# bloodhound_gprs_0_beta.net
KiCad netlist of a schematic drawn in Altium Designer
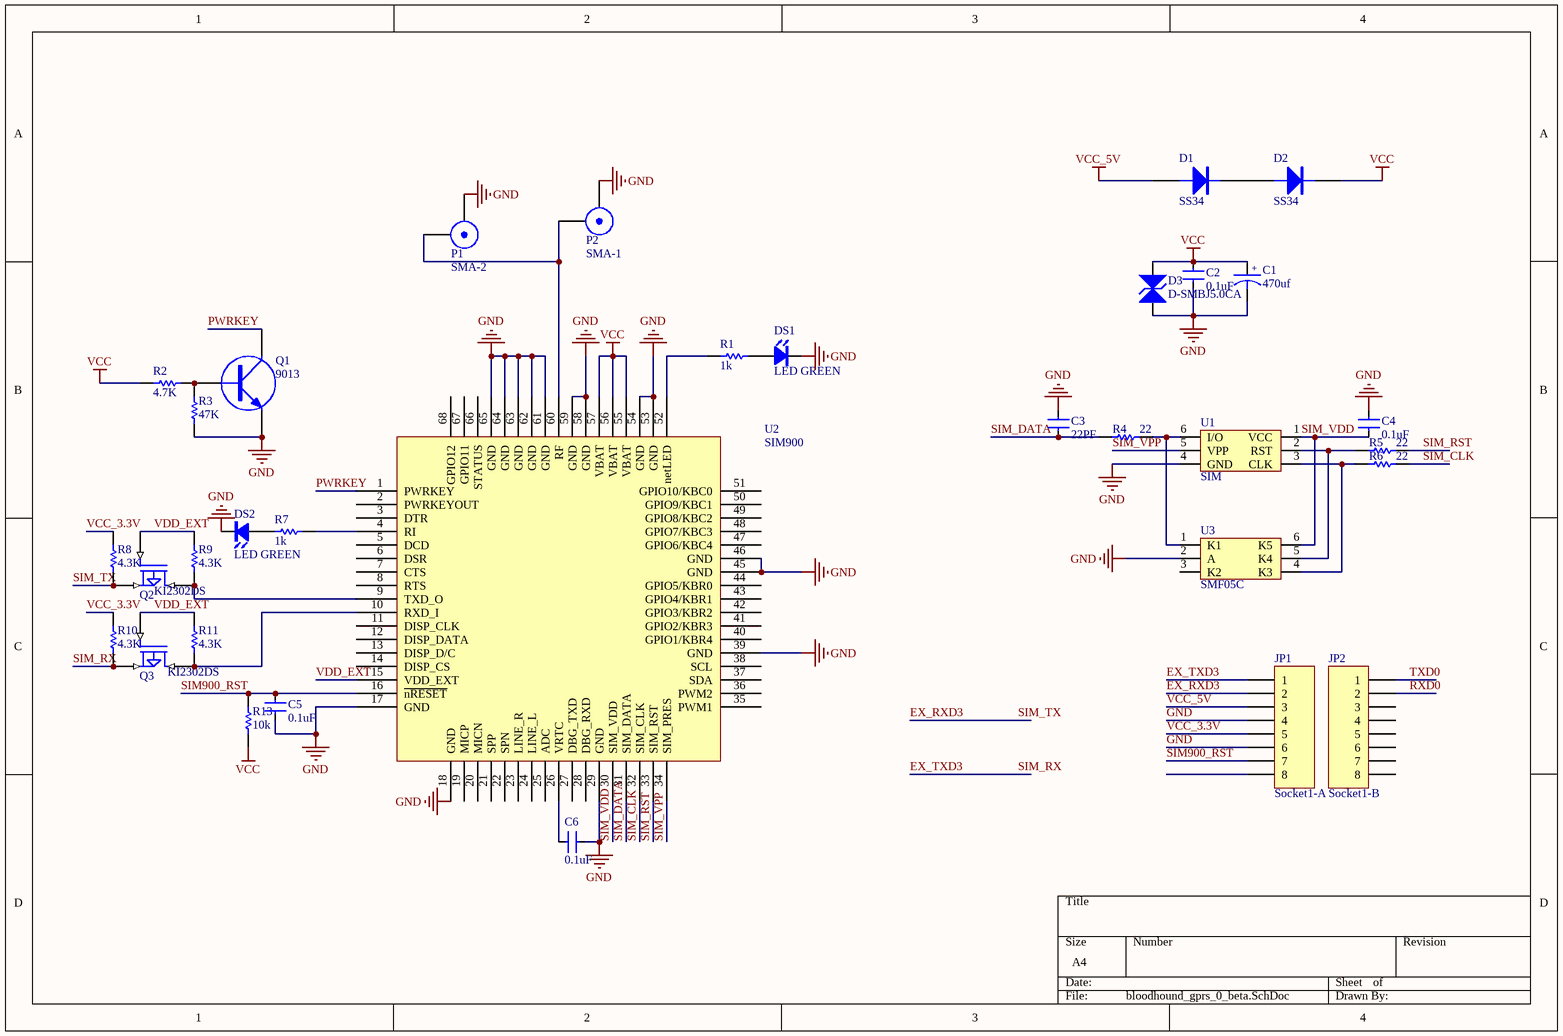
[diagram p0: bloodhound_gprs_0_beta.SchDoc]

(export (version "E")
  (design (tool "Eeschema 10.0.6"))
  (components
    (comp (ref "C1")
      (value "470uf")
      (footprint "C7343")
      (description "钽电容")
      (libsource (lib "BH_DESIGN_DEVICE") (part "CAP-T"))
    )
    (comp (ref "C2")
      (value "0.1uF")
      (footprint "C0603")
      (description "SMD-CAP")
      (libsource (lib "BH_DESIGN_DEVICE") (part "CAP-SMD"))
    )
    (comp (ref "C3")
      (value "22PF")
      (footprint "C0603")
      (description "SMD-CAP")
      (libsource (lib "BH_DESIGN_DEVICE") (part "CAP-SMD"))
    )
    (comp (ref "C4")
      (value "0.1uF")
      (footprint "C0603")
      (description "SMD-CAP")
      (libsource (lib "BH_DESIGN_DEVICE") (part "CAP-SMD"))
    )
    (comp (ref "C5")
      (value "0.1uF")
      (footprint "C0603")
      (description "SMD-CAP")
      (libsource (lib "BH_DESIGN_DEVICE") (part "CAP-SMD"))
    )
    (comp (ref "C6")
      (value "0.1uF")
      (footprint "C0603")
      (description "SMD-CAP")
      (libsource (lib "BH_DESIGN_DEVICE") (part "CAP-SMD"))
    )
    (comp (ref "D1")
      (value "SS34")
      (footprint "DO-214")
      (description "Diode")
      (libsource (lib "BH_DESIGN_DEVICE") (part "DIODE"))
    )
    (comp (ref "D2")
      (value "SS34")
      (footprint "DO-214")
      (description "Diode")
      (libsource (lib "BH_DESIGN_DEVICE") (part "DIODE"))
    )
    (comp (ref "D3")
      (value "D-SMBJ5.0CA")
      (footprint "DO-214")
      (description "TVS")
      (libsource (lib "BH_DESIGN_DEVICE") (part "D-SMBJ5.0CA"))
    )
    (comp (ref "DS1") (value "LED GREEN") (footprint "D0805") (libsource (lib "") (part "LED_1")))
    (comp (ref "DS2")
      (value "LED GREEN")
      (footprint "D0805")
      (libsource (lib "BH_DESIGN_DEVICE") (part "LED"))
    )
    (comp (ref "JP1")
      (value "Socket1-A")
      (footprint "SIP1x8x2.54")
      (description "2.0排针")
      (libsource (lib "5D_CONNECTOR") (part "SIP1X8"))
    )
    (comp (ref "JP2")
      (value "Socket1-B")
      (footprint "SIP1x8x2.54")
      (description "2.0排针")
      (libsource (lib "") (part "SIP1X8_1"))
    )
    (comp (ref "P1")
      (value "SMA-2")
      (footprint "IPX")
      (description "IPX")
      (libsource (lib "BH_DESIGN_CONNECTOR") (part "BNC"))
    )
    (comp (ref "P2")
      (value "SMA-1")
      (footprint "SMA-2")
      (description "SMB-KWE")
      (libsource (lib "") (part "BNC_1"))
    )
    (comp (ref "Q1")
      (value "9013")
      (footprint "SOT23-3L")
      (description "NPN Transistor")
      (libsource (lib "BH_DESIGN_DEVICE") (part "NPN"))
    )
    (comp (ref "Q2")
      (value "KI2302DS")
      (footprint "TSMT3")
      (description "N MOSFET")
      (libsource (lib "BH_DESIGN_DEVICE") (part "MOSFET P"))
    )
    (comp (ref "Q3")
      (value "KI2302DS")
      (footprint "TSMT3")
      (description "N MOSFET")
      (libsource (lib "BH_DESIGN_DEVICE") (part "MOSFET P"))
    )
    (comp (ref "R1")
      (value "1k")
      (footprint "R0603")
      (description "Resistor")
      (libsource (lib "BH_DESIGN_DEVICE") (part "RES"))
    )
    (comp (ref "R2")
      (value "4.7K")
      (footprint "R0603")
      (description "Resistor")
      (libsource (lib "BH_DESIGN_DEVICE") (part "RES"))
    )
    (comp (ref "R3")
      (value "47K")
      (footprint "R0603")
      (description "Resistor")
      (libsource (lib "BH_DESIGN_DEVICE") (part "RES"))
    )
    (comp (ref "R4")
      (value "22")
      (footprint "R0603")
      (description "Resistor")
      (libsource (lib "BH_DESIGN_DEVICE") (part "RES"))
    )
    (comp (ref "R5")
      (value "22")
      (footprint "R0603")
      (description "Resistor")
      (libsource (lib "BH_DESIGN_DEVICE") (part "RES"))
    )
    (comp (ref "R6")
      (value "22")
      (footprint "R0603")
      (description "Resistor")
      (libsource (lib "BH_DESIGN_DEVICE") (part "RES"))
    )
    (comp (ref "R7")
      (value "1k")
      (footprint "R0603")
      (description "Resistor")
      (libsource (lib "BH_DESIGN_DEVICE") (part "RES"))
    )
    (comp (ref "R8")
      (value "4.3K")
      (footprint "R0603")
      (description "Resistor")
      (libsource (lib "BH_DESIGN_DEVICE") (part "RES"))
    )
    (comp (ref "R9")
      (value "4.3K")
      (footprint "R0603")
      (description "Resistor")
      (libsource (lib "BH_DESIGN_DEVICE") (part "RES"))
    )
    (comp (ref "R10")
      (value "4.3K")
      (footprint "R0603")
      (description "Resistor")
      (libsource (lib "BH_DESIGN_DEVICE") (part "RES"))
    )
    (comp (ref "R11")
      (value "4.3K")
      (footprint "R0603")
      (description "Resistor")
      (libsource (lib "BH_DESIGN_DEVICE") (part "RES"))
    )
    (comp (ref "R13")
      (value "10k")
      (footprint "R0603")
      (description "Resistor")
      (libsource (lib "BH_DESIGN_DEVICE") (part "RES"))
    )
    (comp (ref "U1")
      (value "SIM")
      (footprint "SIM")
      (description "手机SIM卡")
      (libsource (lib "BH_DESIGN_CONNECTOR") (part "SIM"))
    )
    (comp (ref "U2")
      (value "SIM900")
      (footprint "GSM_900A")
      (libsource (lib "BH_DESIGN_DEVICE") (part "SIM900"))
    )
    (comp (ref "U3")
      (value "SMF05C")
      (footprint "SOT-363")
      (description "TVS")
      (libsource (lib "SIM900_MD") (part "SMF05C"))
    )
  )
  (nets
    (net (code "1") (name "/EX_RXD3") (class "Default")
      (node (ref "JP1") (pin "2") (pinfunction "2_2") (pintype "passive"))
      (node (ref "Q2") (pin "3") (pinfunction "S_3") (pintype "input"))
      (node (ref "R8") (pin "2") (pinfunction "2_2") (pintype "passive"))
    )
    (net (code "2") (name "/EX_TXD3") (class "Default")
      (node (ref "JP1") (pin "1") (pinfunction "1_1") (pintype "passive"))
      (node (ref "Q3") (pin "3") (pinfunction "S_3") (pintype "input"))
      (node (ref "R10") (pin "2") (pinfunction "2_2") (pintype "passive"))
    )
    (net (code "3") (name "/PWRKEY") (class "Default")
      (node (ref "Q1") (pin "C") (pinfunction "C_C") (pintype "passive"))
      (node (ref "U2") (pin "1") (pinfunction "PWRKEY_1") (pintype "passive"))
    )
    (net (code "4") (name "/RXD0") (class "Default")
      (node (ref "JP2") (pin "2") (pinfunction "2_2") (pintype "passive"))
    )
    (net (code "5") (name "/SIM900_RST") (class "Default")
      (node (ref "C5") (pin "1") (pinfunction "1_1") (pintype "passive"))
      (node (ref "JP1") (pin "7") (pinfunction "7_7") (pintype "passive"))
      (node (ref "R13") (pin "1") (pinfunction "1_1") (pintype "passive"))
      (node (ref "U2") (pin "16") (pinfunction "~{nRESET}_16") (pintype "passive"))
    )
    (net (code "6") (name "/SIM_CLK") (class "Default")
      (node (ref "R6") (pin "1") (pinfunction "1_1") (pintype "passive"))
      (node (ref "U2") (pin "32") (pinfunction "SIM_CLK_32") (pintype "passive"))
    )
    (net (code "7") (name "/SIM_DATA") (class "Default")
      (node (ref "C3") (pin "1") (pinfunction "1_1") (pintype "passive"))
      (node (ref "R4") (pin "2") (pinfunction "2_2") (pintype "passive"))
      (node (ref "U2") (pin "31") (pinfunction "SIM_DATA_31") (pintype "passive"))
    )
    (net (code "8") (name "/SIM_RST") (class "Default")
      (node (ref "R5") (pin "1") (pinfunction "1_1") (pintype "passive"))
      (node (ref "U2") (pin "33") (pinfunction "SIM_RST_33") (pintype "passive"))
    )
    (net (code "9") (name "/SIM_VDD") (class "Default")
      (node (ref "C4") (pin "1") (pinfunction "1_1") (pintype "passive"))
      (node (ref "U1") (pin "1") (pinfunction "VCC_1") (pintype "passive"))
      (node (ref "U2") (pin "30") (pinfunction "SIM_VDD_30") (pintype "passive"))
      (node (ref "U3") (pin "6") (pinfunction "K5_6") (pintype "passive"))
    )
    (net (code "10") (name "/SIM_VPP") (class "Default")
      (node (ref "U1") (pin "5") (pinfunction "VPP_5") (pintype "passive"))
      (node (ref "U2") (pin "34") (pinfunction "SIM_PRES_34") (pintype "passive"))
    )
    (net (code "11") (name "/TXD0") (class "Default")
      (node (ref "JP2") (pin "1") (pinfunction "1_1") (pintype "passive"))
    )
    (net (code "12") (name "/VCC_3.3V") (class "Default")
      (node (ref "JP1") (pin "5") (pinfunction "5_5") (pintype "passive"))
      (node (ref "R10") (pin "1") (pinfunction "1_1") (pintype "passive"))
      (node (ref "R8") (pin "1") (pinfunction "1_1") (pintype "passive"))
    )
    (net (code "13") (name "/VDD_EXT") (class "Default")
      (node (ref "Q2") (pin "1") (pinfunction "G_1") (pintype "input"))
      (node (ref "Q3") (pin "1") (pinfunction "G_1") (pintype "input"))
      (node (ref "R11") (pin "1") (pinfunction "1_1") (pintype "passive"))
      (node (ref "R9") (pin "1") (pinfunction "1_1") (pintype "passive"))
      (node (ref "U2") (pin "15") (pinfunction "VDD_EXT_15") (pintype "passive"))
    )
    (net (code "14") (name "GND") (class "Default")
      (node (ref "C1") (pin "2") (pinfunction "2_2") (pintype "passive"))
      (node (ref "C2") (pin "1") (pinfunction "1_1") (pintype "passive"))
      (node (ref "C3") (pin "2") (pinfunction "2_2") (pintype "passive"))
      (node (ref "C4") (pin "2") (pinfunction "2_2") (pintype "passive"))
      (node (ref "C5") (pin "2") (pinfunction "2_2") (pintype "passive"))
      (node (ref "C6") (pin "2") (pinfunction "2_2") (pintype "passive"))
      (node (ref "D3") (pin "A") (pinfunction "1_A") (pintype "passive"))
      (node (ref "DS1") (pin "K") (pinfunction "2_K") (pintype "passive"))
      (node (ref "DS2") (pin "K") (pinfunction "2_K") (pintype "passive"))
      (node (ref "JP1") (pin "4") (pinfunction "4_4") (pintype "passive"))
      (node (ref "JP1") (pin "6") (pinfunction "6_6") (pintype "passive"))
      (node (ref "P1") (pin "2") (pinfunction "Y_2") (pintype "passive"))
      (node (ref "P2") (pin "2") (pinfunction "Y_2") (pintype "passive"))
      (node (ref "Q1") (pin "E") (pinfunction "E_E") (pintype "passive"))
      (node (ref "R3") (pin "1") (pinfunction "1_1") (pintype "passive"))
      (node (ref "U1") (pin "4") (pinfunction "GND_4") (pintype "passive"))
      (node (ref "U2") (pin "17") (pinfunction "GND_17") (pintype "passive"))
      (node (ref "U2") (pin "18") (pinfunction "GND_18") (pintype "passive"))
      (node (ref "U2") (pin "29") (pinfunction "GND_29") (pintype "passive"))
      (node (ref "U2") (pin "39") (pinfunction "GND_39") (pintype "passive"))
      (node (ref "U2") (pin "45") (pinfunction "GND_45") (pintype "passive"))
      (node (ref "U2") (pin "46") (pinfunction "GND_46") (pintype "passive"))
      (node (ref "U2") (pin "53") (pinfunction "GND_53") (pintype "passive"))
      (node (ref "U2") (pin "54") (pinfunction "GND_54") (pintype "passive"))
      (node (ref "U2") (pin "58") (pinfunction "GND_58") (pintype "passive"))
      (node (ref "U2") (pin "59") (pinfunction "GND_59") (pintype "passive"))
      (node (ref "U2") (pin "61") (pinfunction "GND_61") (pintype "passive"))
      (node (ref "U2") (pin "62") (pinfunction "GND_62") (pintype "passive"))
      (node (ref "U2") (pin "63") (pinfunction "GND_63") (pintype "passive"))
      (node (ref "U2") (pin "64") (pinfunction "GND_64") (pintype "passive"))
      (node (ref "U2") (pin "65") (pinfunction "GND_65") (pintype "passive"))
      (node (ref "U3") (pin "2") (pinfunction "A_2") (pintype "passive"))
    )
    (net (code "15") (name "Net-(D1-K)") (class "Default")
      (node (ref "D1") (pin "2") (pinfunction "K_2") (pintype "passive"))
      (node (ref "D2") (pin "1") (pinfunction "A_1") (pintype "passive"))
    )
    (net (code "16") (name "Net-(DS1-1)") (class "Default")
      (node (ref "DS1") (pin "A") (pinfunction "1_A") (pintype "passive"))
      (node (ref "R1") (pin "1") (pinfunction "1_1") (pintype "passive"))
    )
    (net (code "17") (name "Net-(DS2-1)") (class "Default")
      (node (ref "DS2") (pin "A") (pinfunction "1_A") (pintype "passive"))
      (node (ref "R7") (pin "1") (pinfunction "1_1") (pintype "passive"))
    )
    (net (code "18") (name "Net-(P1-X)") (class "Default")
      (node (ref "P1") (pin "1") (pinfunction "X_1") (pintype "passive"))
      (node (ref "P2") (pin "1") (pinfunction "X_1") (pintype "passive"))
      (node (ref "U2") (pin "60") (pinfunction "RF_60") (pintype "passive"))
    )
    (net (code "19") (name "Net-(Q1-PadB)") (class "Default")
      (node (ref "Q1") (pin "B") (pinfunction "B_B") (pintype "passive"))
      (node (ref "R2") (pin "2") (pinfunction "2_2") (pintype "passive"))
      (node (ref "R3") (pin "2") (pinfunction "2_2") (pintype "passive"))
    )
    (net (code "20") (name "Net-(Q2-D)") (class "Default")
      (node (ref "Q2") (pin "2") (pinfunction "D_2") (pintype "input"))
      (node (ref "R9") (pin "2") (pinfunction "2_2") (pintype "passive"))
      (node (ref "U2") (pin "9") (pinfunction "TXD_O_9") (pintype "passive"))
    )
    (net (code "21") (name "Net-(Q3-D)") (class "Default")
      (node (ref "Q3") (pin "2") (pinfunction "D_2") (pintype "input"))
      (node (ref "R11") (pin "2") (pinfunction "2_2") (pintype "passive"))
      (node (ref "U2") (pin "10") (pinfunction "RXD_I_10") (pintype "passive"))
    )
    (net (code "22") (name "Net-(U1-CLK)") (class "Default")
      (node (ref "R6") (pin "2") (pinfunction "2_2") (pintype "passive"))
      (node (ref "U1") (pin "3") (pinfunction "CLK_3") (pintype "passive"))
      (node (ref "U3") (pin "4") (pinfunction "K3_4") (pintype "passive"))
    )
    (net (code "23") (name "Net-(U1-I{slash}O)") (class "Default")
      (node (ref "R4") (pin "1") (pinfunction "1_1") (pintype "passive"))
      (node (ref "U1") (pin "6") (pinfunction "I/O_6") (pintype "passive"))
      (node (ref "U3") (pin "1") (pinfunction "K1_1") (pintype "passive"))
    )
    (net (code "24") (name "Net-(U1-RST)") (class "Default")
      (node (ref "R5") (pin "2") (pinfunction "2_2") (pintype "passive"))
      (node (ref "U1") (pin "2") (pinfunction "RST_2") (pintype "passive"))
      (node (ref "U3") (pin "5") (pinfunction "K4_5") (pintype "passive"))
    )
    (net (code "25") (name "Net-(U2-RI)") (class "Default")
      (node (ref "R7") (pin "2") (pinfunction "2_2") (pintype "passive"))
      (node (ref "U2") (pin "4") (pinfunction "RI_4") (pintype "passive"))
    )
    (net (code "26") (name "Net-(U2-VRTC)") (class "Default")
      (node (ref "C6") (pin "1") (pinfunction "1_1") (pintype "passive"))
      (node (ref "U2") (pin "26") (pinfunction "VRTC_26") (pintype "passive"))
    )
    (net (code "27") (name "Net-(U2-netLED)") (class "Default")
      (node (ref "R1") (pin "2") (pinfunction "2_2") (pintype "passive"))
      (node (ref "U2") (pin "52") (pinfunction "netLED_52") (pintype "passive"))
    )
    (net (code "28") (name "VCC") (class "Default")
      (node (ref "C1") (pin "1") (pinfunction "1_1") (pintype "passive"))
      (node (ref "C2") (pin "2") (pinfunction "2_2") (pintype "passive"))
      (node (ref "D2") (pin "2") (pinfunction "K_2") (pintype "passive"))
      (node (ref "D3") (pin "K") (pinfunction "2_K") (pintype "passive"))
      (node (ref "R13") (pin "2") (pinfunction "2_2") (pintype "passive"))
      (node (ref "R2") (pin "1") (pinfunction "1_1") (pintype "passive"))
      (node (ref "U2") (pin "55") (pinfunction "VBAT_55") (pintype "passive"))
      (node (ref "U2") (pin "56") (pinfunction "VBAT_56") (pintype "passive"))
      (node (ref "U2") (pin "57") (pinfunction "VBAT_57") (pintype "passive"))
    )
    (net (code "29") (name "VCC_5V") (class "Default")
      (node (ref "D1") (pin "1") (pinfunction "A_1") (pintype "passive"))
      (node (ref "JP1") (pin "3") (pinfunction "3_3") (pintype "passive"))
    )
    (net (code "30") (name "unconnected-(JP1-Pad8)") (class "Default")
      (node (ref "JP1") (pin "8") (pinfunction "8_8") (pintype "passive"))
    )
    (net (code "31") (name "unconnected-(JP2-Pad3)") (class "Default")
      (node (ref "JP2") (pin "3") (pinfunction "3_3") (pintype "passive"))
    )
    (net (code "32") (name "unconnected-(JP2-Pad4)") (class "Default")
      (node (ref "JP2") (pin "4") (pinfunction "4_4") (pintype "passive"))
    )
    (net (code "33") (name "unconnected-(JP2-Pad5)") (class "Default")
      (node (ref "JP2") (pin "5") (pinfunction "5_5") (pintype "passive"))
    )
    (net (code "34") (name "unconnected-(JP2-Pad6)") (class "Default")
      (node (ref "JP2") (pin "6") (pinfunction "6_6") (pintype "passive"))
    )
    (net (code "35") (name "unconnected-(JP2-Pad7)") (class "Default")
      (node (ref "JP2") (pin "7") (pinfunction "7_7") (pintype "passive"))
    )
    (net (code "36") (name "unconnected-(JP2-Pad8)") (class "Default")
      (node (ref "JP2") (pin "8") (pinfunction "8_8") (pintype "passive"))
    )
    (net (code "37") (name "unconnected-(U2-ADC-Pad25)") (class "Default")
      (node (ref "U2") (pin "25") (pinfunction "ADC_25") (pintype "passive"))
    )
    (net (code "38") (name "unconnected-(U2-CTS-Pad7)") (class "Default")
      (node (ref "U2") (pin "7") (pinfunction "CTS_7") (pintype "passive"))
    )
    (net (code "39") (name "unconnected-(U2-DBG_RXD-Pad28)") (class "Default")
      (node (ref "U2") (pin "28") (pinfunction "DBG_RXD_28") (pintype "passive"))
    )
    (net (code "40") (name "unconnected-(U2-DBG_TXD-Pad27)") (class "Default")
      (node (ref "U2") (pin "27") (pinfunction "DBG_TXD_27") (pintype "passive"))
    )
    (net (code "41") (name "unconnected-(U2-DCD-Pad5)") (class "Default")
      (node (ref "U2") (pin "5") (pinfunction "DCD_5") (pintype "passive"))
    )
    (net (code "42") (name "unconnected-(U2-DISP_CLK-Pad11)") (class "Default")
      (node (ref "U2") (pin "11") (pinfunction "DISP_CLK_11") (pintype "passive"))
    )
    (net (code "43") (name "unconnected-(U2-DISP_CS-Pad14)") (class "Default")
      (node (ref "U2") (pin "14") (pinfunction "DISP_CS_14") (pintype "passive"))
    )
    (net (code "44") (name "unconnected-(U2-DISP_DATA-Pad12)") (class "Default")
      (node (ref "U2") (pin "12") (pinfunction "DISP_DATA_12") (pintype "passive"))
    )
    (net (code "45") (name "unconnected-(U2-DISP_D{slash}C-Pad13)") (class "Default")
      (node (ref "U2") (pin "13") (pinfunction "DISP_D/C_13") (pintype "passive"))
    )
    (net (code "46") (name "unconnected-(U2-DSR-Pad6)") (class "Default")
      (node (ref "U2") (pin "6") (pinfunction "DSR_6") (pintype "passive"))
    )
    (net (code "47") (name "unconnected-(U2-DTR-Pad3)") (class "Default")
      (node (ref "U2") (pin "3") (pinfunction "DTR_3") (pintype "passive"))
    )
    (net (code "48") (name "unconnected-(U2-GPIO1{slash}KBR4-Pad40)") (class "Default")
      (node (ref "U2") (pin "40") (pinfunction "GPIO1/KBR4_40") (pintype "passive"))
    )
    (net (code "49") (name "unconnected-(U2-GPIO2{slash}KBR3-Pad41)") (class "Default")
      (node (ref "U2") (pin "41") (pinfunction "GPIO2/KBR3_41") (pintype "passive"))
    )
    (net (code "50") (name "unconnected-(U2-GPIO3{slash}KBR2-Pad42)") (class "Default")
      (node (ref "U2") (pin "42") (pinfunction "GPIO3/KBR2_42") (pintype "passive"))
    )
    (net (code "51") (name "unconnected-(U2-GPIO4{slash}KBR1-Pad43)") (class "Default")
      (node (ref "U2") (pin "43") (pinfunction "GPIO4/KBR1_43") (pintype "passive"))
    )
    (net (code "52") (name "unconnected-(U2-GPIO5{slash}KBR0-Pad44)") (class "Default")
      (node (ref "U2") (pin "44") (pinfunction "GPIO5/KBR0_44") (pintype "passive"))
    )
    (net (code "53") (name "unconnected-(U2-GPIO6{slash}KBC4-Pad47)") (class "Default")
      (node (ref "U2") (pin "47") (pinfunction "GPIO6/KBC4_47") (pintype "passive"))
    )
    (net (code "54") (name "unconnected-(U2-GPIO7{slash}KBC3-Pad48)") (class "Default")
      (node (ref "U2") (pin "48") (pinfunction "GPIO7/KBC3_48") (pintype "passive"))
    )
    (net (code "55") (name "unconnected-(U2-GPIO8{slash}KBC2-Pad49)") (class "Default")
      (node (ref "U2") (pin "49") (pinfunction "GPIO8/KBC2_49") (pintype "passive"))
    )
    (net (code "56") (name "unconnected-(U2-GPIO9{slash}KBC1-Pad50)") (class "Default")
      (node (ref "U2") (pin "50") (pinfunction "GPIO9/KBC1_50") (pintype "passive"))
    )
    (net (code "57") (name "unconnected-(U2-GPIO10{slash}KBC0-Pad51)") (class "Default")
      (node (ref "U2") (pin "51") (pinfunction "GPIO10/KBC0_51") (pintype "passive"))
    )
    (net (code "58") (name "unconnected-(U2-GPIO11-Pad67)") (class "Default")
      (node (ref "U2") (pin "67") (pinfunction "GPIO11_67") (pintype "passive"))
    )
    (net (code "59") (name "unconnected-(U2-GPIO12-Pad68)") (class "Default")
      (node (ref "U2") (pin "68") (pinfunction "GPIO12_68") (pintype "passive"))
    )
    (net (code "60") (name "unconnected-(U2-LINE_L-Pad24)") (class "Default")
      (node (ref "U2") (pin "24") (pinfunction "LINE_L_24") (pintype "passive"))
    )
    (net (code "61") (name "unconnected-(U2-LINE_R-Pad23)") (class "Default")
      (node (ref "U2") (pin "23") (pinfunction "LINE_R_23") (pintype "passive"))
    )
    (net (code "62") (name "unconnected-(U2-MICN-Pad20)") (class "Default")
      (node (ref "U2") (pin "20") (pinfunction "MICN_20") (pintype "passive"))
    )
    (net (code "63") (name "unconnected-(U2-MICP-Pad19)") (class "Default")
      (node (ref "U2") (pin "19") (pinfunction "MICP_19") (pintype "passive"))
    )
    (net (code "64") (name "unconnected-(U2-PWM1-Pad35)") (class "Default")
      (node (ref "U2") (pin "35") (pinfunction "PWM1_35") (pintype "passive"))
    )
    (net (code "65") (name "unconnected-(U2-PWM2-Pad36)") (class "Default")
      (node (ref "U2") (pin "36") (pinfunction "PWM2_36") (pintype "passive"))
    )
    (net (code "66") (name "unconnected-(U2-PWRKEYOUT-Pad2)") (class "Default")
      (node (ref "U2") (pin "2") (pinfunction "PWRKEYOUT_2") (pintype "passive"))
    )
    (net (code "67") (name "unconnected-(U2-RTS-Pad8)") (class "Default")
      (node (ref "U2") (pin "8") (pinfunction "RTS_8") (pintype "passive"))
    )
    (net (code "68") (name "unconnected-(U2-SCL-Pad38)") (class "Default")
      (node (ref "U2") (pin "38") (pinfunction "SCL_38") (pintype "passive"))
    )
    (net (code "69") (name "unconnected-(U2-SDA-Pad37)") (class "Default")
      (node (ref "U2") (pin "37") (pinfunction "SDA_37") (pintype "passive"))
    )
    (net (code "70") (name "unconnected-(U2-SPN-Pad22)") (class "Default")
      (node (ref "U2") (pin "22") (pinfunction "SPN_22") (pintype "passive"))
    )
    (net (code "71") (name "unconnected-(U2-SPP-Pad21)") (class "Default")
      (node (ref "U2") (pin "21") (pinfunction "SPP_21") (pintype "passive"))
    )
    (net (code "72") (name "unconnected-(U2-STATUS-Pad66)") (class "Default")
      (node (ref "U2") (pin "66") (pinfunction "STATUS_66") (pintype "passive"))
    )
    (net (code "73") (name "unconnected-(U3-K2-Pad3)") (class "Default")
      (node (ref "U3") (pin "3") (pinfunction "K2_3") (pintype "passive"))
    )
  )
)
